# v6_io_23_24_25_26.net
KiCad netlist of a schematic drawn in Altium Designer
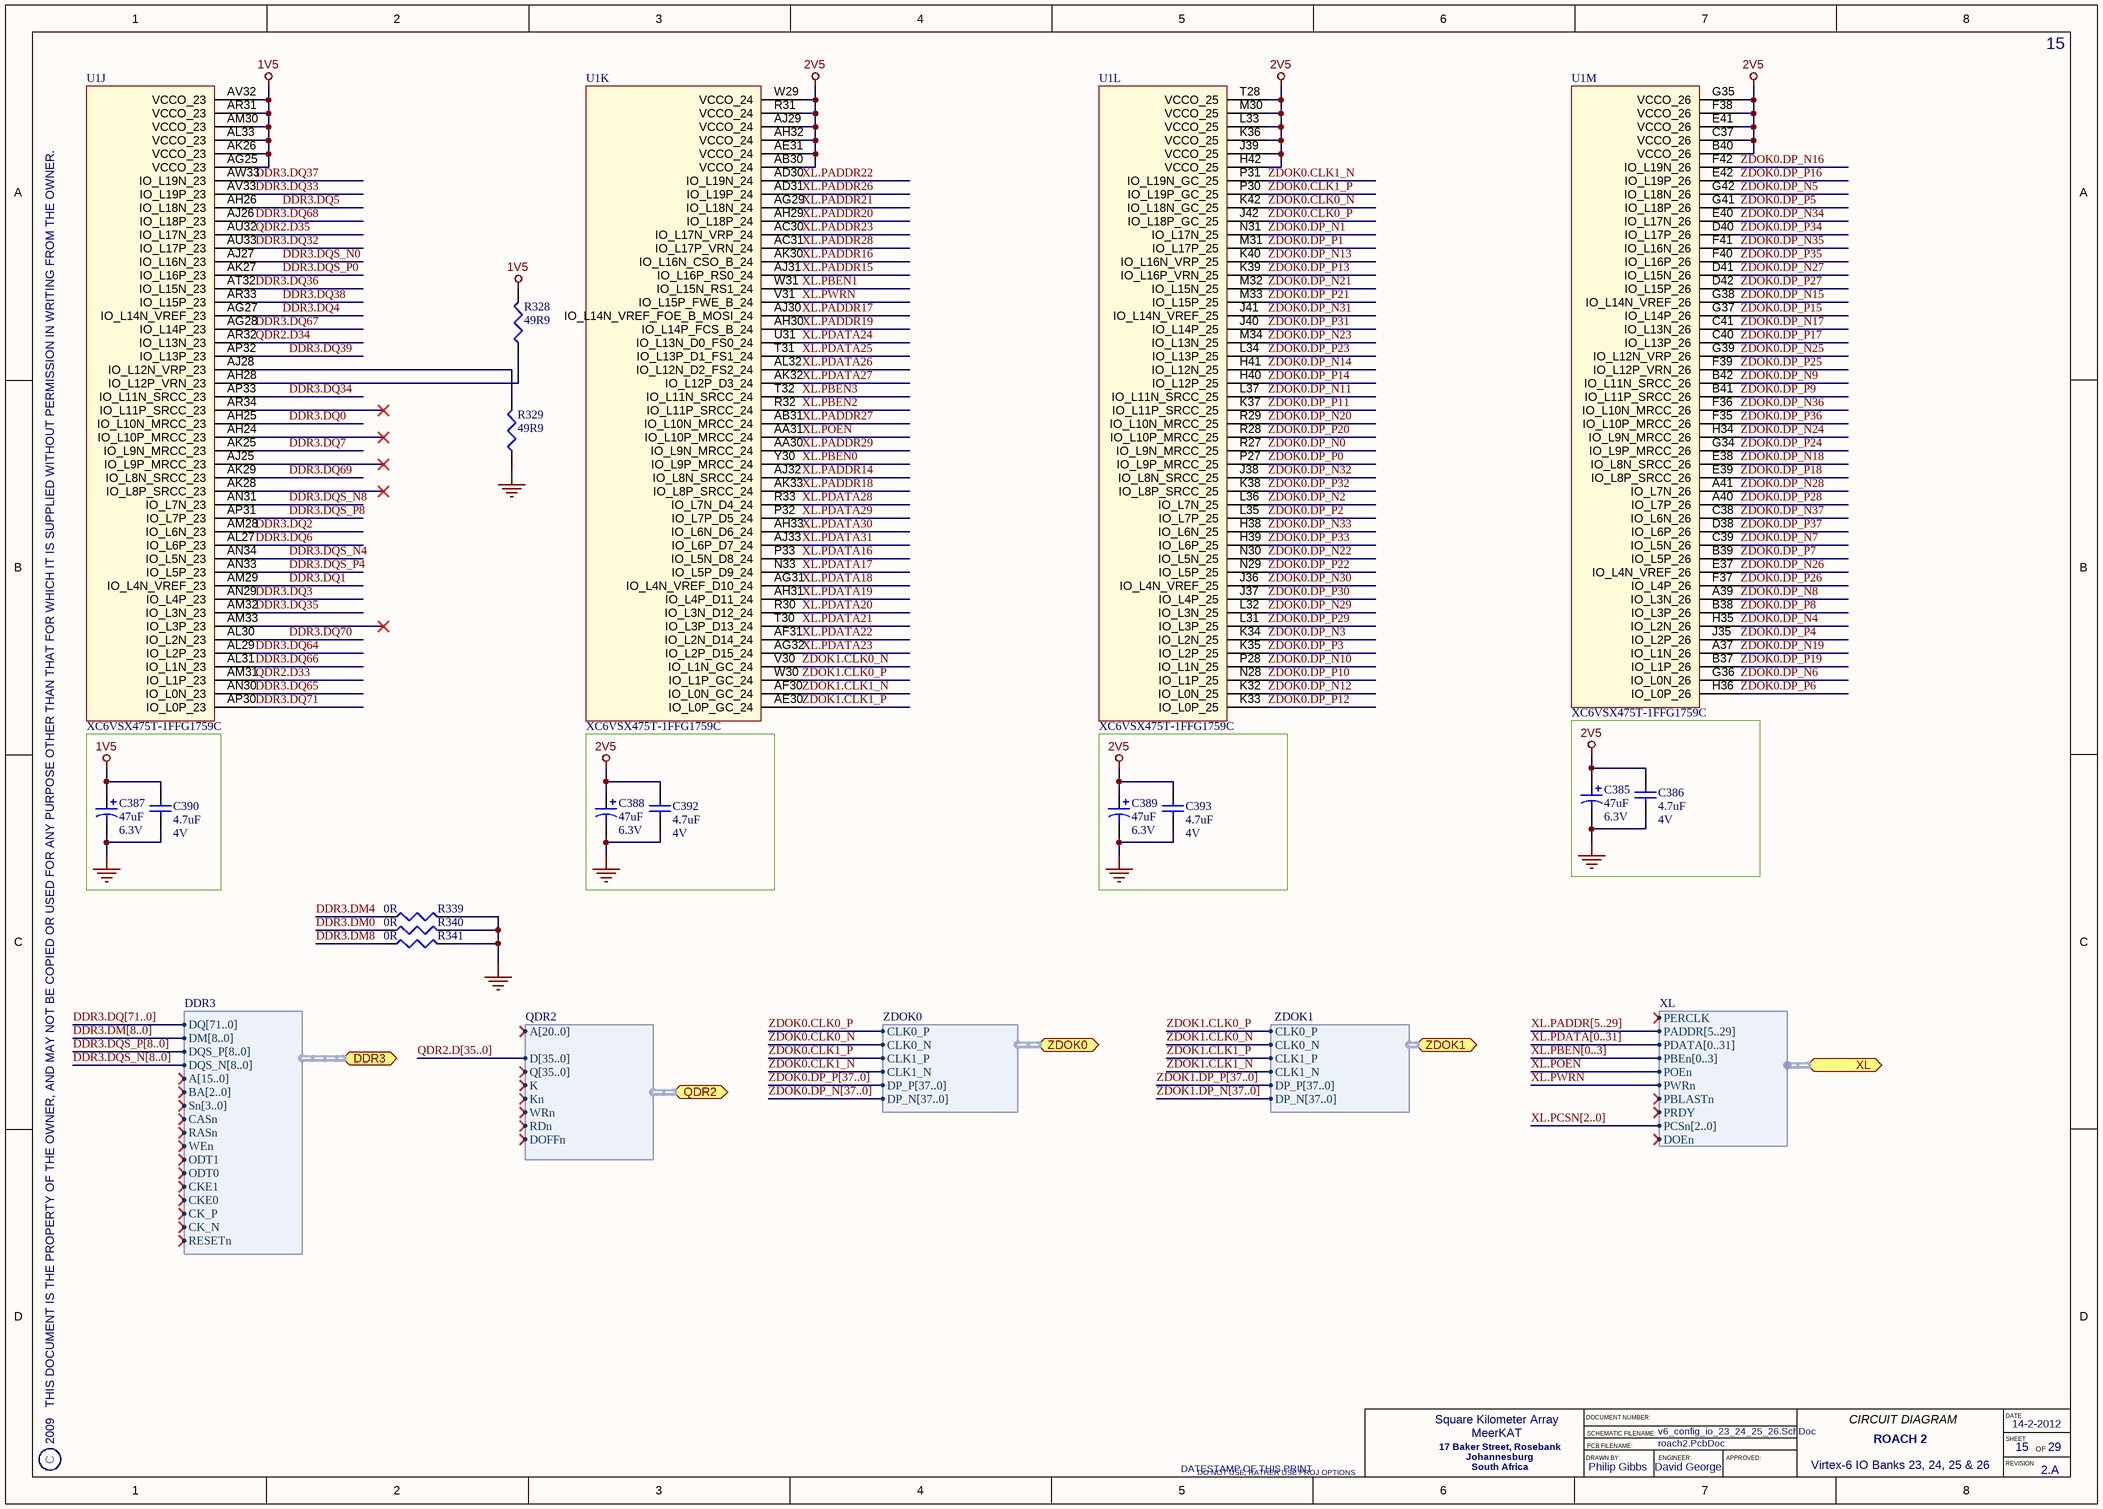
[diagram p0: v6_io_23_24_25_26.SchDoc]

(export (version "E")
  (design (tool "Eeschema 10.0.6"))
  (components
    (comp (ref "C385")
      (value "47uF")
      (footprint "CAPMP3528X120L")
      (description "47uF, Conductive Polymer Chip Capacitor")
      (fields
        (field (name "RATING") "6.3V")
        (field (name "MANUFACTURER") "KEMET")
        (field (name "PARTNUM") "T520T476M006ATE070")
      )
      (libsource (lib "altium_db") (part "CapPol"))
    )
    (comp (ref "C386")
      (value "4.7uF")
      (footprint "CAPC1005X60L")
      (description "4.7uF, Ceramic Capacitor")
      (fields
        (field (name "RATING") "4V")
        (field (name "MANUFACTURER") "MURATA")
        (field (name "PARTNUM") "AMK105BJ475MV-F")
      )
      (libsource (lib "altium_db") (part "CapStd"))
    )
    (comp (ref "C387")
      (value "47uF")
      (footprint "CAPMP3528X120L")
      (description "47uF, Conductive Polymer Chip Capacitor")
      (fields
        (field (name "RATING") "6.3V")
        (field (name "MANUFACTURER") "KEMET")
        (field (name "PARTNUM") "T520T476M006ATE070")
      )
      (libsource (lib "altium_db") (part "CapPol"))
    )
    (comp (ref "C388")
      (value "47uF")
      (footprint "CAPMP3528X120L")
      (description "47uF, Conductive Polymer Chip Capacitor")
      (fields
        (field (name "RATING") "6.3V")
        (field (name "MANUFACTURER") "KEMET")
        (field (name "PARTNUM") "T520T476M006ATE070")
      )
      (libsource (lib "altium_db") (part "CapPol"))
    )
    (comp (ref "C389")
      (value "47uF")
      (footprint "CAPMP3528X120L")
      (description "47uF, Conductive Polymer Chip Capacitor")
      (fields
        (field (name "RATING") "6.3V")
        (field (name "MANUFACTURER") "KEMET")
        (field (name "PARTNUM") "T520T476M006ATE070")
      )
      (libsource (lib "altium_db") (part "CapPol"))
    )
    (comp (ref "C390")
      (value "4.7uF")
      (footprint "CAPC1005X60L")
      (description "4.7uF, Ceramic Capacitor")
      (fields
        (field (name "RATING") "4V")
        (field (name "MANUFACTURER") "MURATA")
        (field (name "PARTNUM") "AMK105BJ475MV-F")
      )
      (libsource (lib "altium_db") (part "CapStd"))
    )
    (comp (ref "C392")
      (value "4.7uF")
      (footprint "CAPC1005X60L")
      (description "4.7uF, Ceramic Capacitor")
      (fields
        (field (name "RATING") "4V")
        (field (name "MANUFACTURER") "MURATA")
        (field (name "PARTNUM") "AMK105BJ475MV-F")
      )
      (libsource (lib "altium_db") (part "CapStd"))
    )
    (comp (ref "C393")
      (value "4.7uF")
      (footprint "CAPC1005X60L")
      (description "4.7uF, Ceramic Capacitor")
      (fields
        (field (name "RATING") "4V")
        (field (name "MANUFACTURER") "MURATA")
        (field (name "PARTNUM") "AMK105BJ475MV-F")
      )
      (libsource (lib "altium_db") (part "CapStd"))
    )
    (comp (ref "R328")
      (value "49R9")
      (footprint "RESC1005X40L")
      (description "49R9, 1.1mm x 0.5mm, Thick Film Resistor")
      (fields (field (name "MANUFACTURER") "ROYALOHM") (field (name "PARTNUM") "0402WGF499JT1E"))
      (libsource (lib "altium_db") (part "ResStd"))
    )
    (comp (ref "R329")
      (value "49R9")
      (footprint "RESC1005X40L")
      (description "49R9, 1.1mm x 0.5mm, Thick Film Resistor")
      (fields (field (name "MANUFACTURER") "ROYALOHM") (field (name "PARTNUM") "0402WGF499JT1E"))
      (libsource (lib "altium_db") (part "ResStd"))
    )
    (comp (ref "R339")
      (value "0R")
      (footprint "RESC1005X40L")
      (description "0R, 1.1mm x 0.5mm, Thick Film Resistor")
      (fields (field (name "MANUFACTURER") "ROYALOHM") (field (name "PARTNUM") "0402WG00000T1E"))
      (libsource (lib "altium_db") (part "ResStd"))
    )
    (comp (ref "R340")
      (value "0R")
      (footprint "RESC1005X40L")
      (description "0R, 1.1mm x 0.5mm, Thick Film Resistor")
      (fields (field (name "MANUFACTURER") "ROYALOHM") (field (name "PARTNUM") "0402WG00000T1E"))
      (libsource (lib "altium_db") (part "ResStd"))
    )
    (comp (ref "R341")
      (value "0R")
      (footprint "RESC1005X40L")
      (description "0R, 1.1mm x 0.5mm, Thick Film Resistor")
      (fields (field (name "MANUFACTURER") "ROYALOHM") (field (name "PARTNUM") "0402WG00000T1E"))
      (libsource (lib "altium_db") (part "ResStd"))
    )
    (comp (ref "U1")
      (value "XC6VSX475T-1FFG1759C")
      (footprint "FFG1759")
      (description "Virtex-6 475SXT 1760-pin FPGA")
      (fields (field (name "MANUFACTURER") "Xilinx"))
      (libsource (lib "altium_db") (part "XC6VSX475T-1FFG1759C"))
    )
  )
  (nets
    (net (code "170") (name "/DDR3.DM0") (class "Default")
      (node (ref "R340") (pin "1") (pinfunction "1_1") (pintype "passive"))
    )
    (net (code "171") (name "/DDR3.DM4") (class "Default")
      (node (ref "R339") (pin "1") (pinfunction "1_1") (pintype "passive"))
    )
    (net (code "172") (name "/DDR3.DM8") (class "Default")
      (node (ref "R341") (pin "1") (pinfunction "1_1") (pintype "passive"))
    )
    (net (code "174") (name "/DDR3.DQ0") (class "Default")
      (node (ref "U1") (pin "AH25") (pinfunction "IO_L10N_MRCC_23_AH25") (pintype "passive"))
    )
    (net (code "175") (name "/DDR3.DQ1") (class "Default")
      (node (ref "U1") (pin "AM29") (pinfunction "IO_L4N_VREF_23_AM29") (pintype "passive"))
    )
    (net (code "176") (name "/DDR3.DQ2") (class "Default")
      (node (ref "U1") (pin "AM28") (pinfunction "IO_L6N_23_AM28") (pintype "passive"))
    )
    (net (code "177") (name "/DDR3.DQ3") (class "Default")
      (node (ref "U1") (pin "AN29") (pinfunction "IO_L4P_23_AN29") (pintype "passive"))
    )
    (net (code "178") (name "/DDR3.DQ4") (class "Default")
      (node (ref "U1") (pin "AG27") (pinfunction "IO_L14N_VREF_23_AG27") (pintype "passive"))
    )
    (net (code "179") (name "/DDR3.DQ5") (class "Default")
      (node (ref "U1") (pin "AH26") (pinfunction "IO_L18N_23_AH26") (pintype "passive"))
    )
    (net (code "180") (name "/DDR3.DQ6") (class "Default")
      (node (ref "U1") (pin "AL27") (pinfunction "IO_L6P_23_AL27") (pintype "passive"))
    )
    (net (code "181") (name "/DDR3.DQ7") (class "Default")
      (node (ref "U1") (pin "AK25") (pinfunction "IO_L9N_MRCC_23_AK25") (pintype "passive"))
    )
    (net (code "182") (name "/DDR3.DQ32") (class "Default")
      (node (ref "U1") (pin "AU33") (pinfunction "IO_L17P_23_AU33") (pintype "passive"))
    )
    (net (code "183") (name "/DDR3.DQ33") (class "Default")
      (node (ref "U1") (pin "AV33") (pinfunction "IO_L19P_23_AV33") (pintype "passive"))
    )
    (net (code "184") (name "/DDR3.DQ34") (class "Default")
      (node (ref "U1") (pin "AP33") (pinfunction "IO_L11N_SRCC_23_AP33") (pintype "passive"))
    )
    (net (code "185") (name "/DDR3.DQ35") (class "Default")
      (node (ref "U1") (pin "AM32") (pinfunction "IO_L3N_23_AM32") (pintype "passive"))
    )
    (net (code "186") (name "/DDR3.DQ36") (class "Default")
      (node (ref "U1") (pin "AT32") (pinfunction "IO_L15N_23_AT32") (pintype "passive"))
    )
    (net (code "187") (name "/DDR3.DQ37") (class "Default")
      (node (ref "U1") (pin "AW33") (pinfunction "IO_L19N_23_AW33") (pintype "passive"))
    )
    (net (code "188") (name "/DDR3.DQ38") (class "Default")
      (node (ref "U1") (pin "AR33") (pinfunction "IO_L15P_23_AR33") (pintype "passive"))
    )
    (net (code "189") (name "/DDR3.DQ39") (class "Default")
      (node (ref "U1") (pin "AP32") (pinfunction "IO_L13P_23_AP32") (pintype "passive"))
    )
    (net (code "190") (name "/DDR3.DQ64") (class "Default")
      (node (ref "U1") (pin "AL29") (pinfunction "IO_L2P_23_AL29") (pintype "passive"))
    )
    (net (code "191") (name "/DDR3.DQ65") (class "Default")
      (node (ref "U1") (pin "AN30") (pinfunction "IO_L0N_23_AN30") (pintype "passive"))
    )
    (net (code "192") (name "/DDR3.DQ66") (class "Default")
      (node (ref "U1") (pin "AL31") (pinfunction "IO_L1N_23_AL31") (pintype "passive"))
    )
    (net (code "193") (name "/DDR3.DQ67") (class "Default")
      (node (ref "U1") (pin "AG28") (pinfunction "IO_L14P_23_AG28") (pintype "passive"))
    )
    (net (code "194") (name "/DDR3.DQ68") (class "Default")
      (node (ref "U1") (pin "AJ26") (pinfunction "IO_L18P_23_AJ26") (pintype "passive"))
    )
    (net (code "195") (name "/DDR3.DQ69") (class "Default")
      (node (ref "U1") (pin "AK29") (pinfunction "IO_L8N_SRCC_23_AK29") (pintype "passive"))
    )
    (net (code "196") (name "/DDR3.DQ70") (class "Default")
      (node (ref "U1") (pin "AL30") (pinfunction "IO_L2N_23_AL30") (pintype "passive"))
    )
    (net (code "197") (name "/DDR3.DQ71") (class "Default")
      (node (ref "U1") (pin "AP30") (pinfunction "IO_L0P_23_AP30") (pintype "passive"))
    )
    (net (code "198") (name "/DDR3.DQS_N0") (class "Default")
      (node (ref "U1") (pin "AJ27") (pinfunction "IO_L16N_23_AJ27") (pintype "passive"))
    )
    (net (code "199") (name "/DDR3.DQS_N4") (class "Default")
      (node (ref "U1") (pin "AN34") (pinfunction "IO_L5N_23_AN34") (pintype "passive"))
    )
    (net (code "200") (name "/DDR3.DQS_N8") (class "Default")
      (node (ref "U1") (pin "AN31") (pinfunction "IO_L7N_23_AN31") (pintype "passive"))
    )
    (net (code "202") (name "/DDR3.DQS_P0") (class "Default")
      (node (ref "U1") (pin "AK27") (pinfunction "IO_L16P_23_AK27") (pintype "passive"))
    )
    (net (code "203") (name "/DDR3.DQS_P4") (class "Default")
      (node (ref "U1") (pin "AN33") (pinfunction "IO_L5P_23_AN33") (pintype "passive"))
    )
    (net (code "204") (name "/DDR3.DQS_P8") (class "Default")
      (node (ref "U1") (pin "AP31") (pinfunction "IO_L7P_23_AP31") (pintype "passive"))
    )
    (net (code "207") (name "/QDR2.D33") (class "Default")
      (node (ref "U1") (pin "AM31") (pinfunction "IO_L1P_23_AM31") (pintype "passive"))
    )
    (net (code "208") (name "/QDR2.D34") (class "Default")
      (node (ref "U1") (pin "AR32") (pinfunction "IO_L13N_23_AR32") (pintype "passive"))
    )
    (net (code "209") (name "/QDR2.D35") (class "Default")
      (node (ref "U1") (pin "AU32") (pinfunction "IO_L17N_23_AU32") (pintype "passive"))
    )
    (net (code "211") (name "/XL.PADDR14") (class "Default")
      (node (ref "U1") (pin "AJ32") (pinfunction "IO_L8N_SRCC_24_AJ32") (pintype "passive"))
    )
    (net (code "212") (name "/XL.PADDR15") (class "Default")
      (node (ref "U1") (pin "AJ31") (pinfunction "IO_L16P_RS0_24_AJ31") (pintype "passive"))
    )
    (net (code "213") (name "/XL.PADDR16") (class "Default")
      (node (ref "U1") (pin "AK30") (pinfunction "IO_L16N_CSO_B_24_AK30") (pintype "passive"))
    )
    (net (code "214") (name "/XL.PADDR17") (class "Default")
      (node (ref "U1") (pin "AJ30") (pinfunction "IO_L14N_VREF_FOE_B_MOSI_24_AJ30") (pintype "passive"))
    )
    (net (code "215") (name "/XL.PADDR18") (class "Default")
      (node (ref "U1") (pin "AK33") (pinfunction "IO_L8P_SRCC_24_AK33") (pintype "passive"))
    )
    (net (code "216") (name "/XL.PADDR19") (class "Default")
      (node (ref "U1") (pin "AH30") (pinfunction "IO_L14P_FCS_B_24_AH30") (pintype "passive"))
    )
    (net (code "217") (name "/XL.PADDR20") (class "Default")
      (node (ref "U1") (pin "AH29") (pinfunction "IO_L18P_24_AH29") (pintype "passive"))
    )
    (net (code "218") (name "/XL.PADDR21") (class "Default")
      (node (ref "U1") (pin "AG29") (pinfunction "IO_L18N_24_AG29") (pintype "passive"))
    )
    (net (code "219") (name "/XL.PADDR22") (class "Default")
      (node (ref "U1") (pin "AD30") (pinfunction "IO_L19N_24_AD30") (pintype "passive"))
    )
    (net (code "220") (name "/XL.PADDR23") (class "Default")
      (node (ref "U1") (pin "AC30") (pinfunction "IO_L17N_VRP_24_AC30") (pintype "passive"))
    )
    (net (code "221") (name "/XL.PADDR26") (class "Default")
      (node (ref "U1") (pin "AD31") (pinfunction "IO_L19P_24_AD31") (pintype "passive"))
    )
    (net (code "222") (name "/XL.PADDR27") (class "Default")
      (node (ref "U1") (pin "AB31") (pinfunction "IO_L10N_MRCC_24_AB31") (pintype "passive"))
    )
    (net (code "223") (name "/XL.PADDR28") (class "Default")
      (node (ref "U1") (pin "AC31") (pinfunction "IO_L17P_VRN_24_AC31") (pintype "passive"))
    )
    (net (code "224") (name "/XL.PADDR29") (class "Default")
      (node (ref "U1") (pin "AA30") (pinfunction "IO_L9N_MRCC_24_AA30") (pintype "passive"))
    )
    (net (code "226") (name "/XL.PBEN0") (class "Default")
      (node (ref "U1") (pin "Y30") (pinfunction "IO_L9P_MRCC_24_Y30") (pintype "passive"))
    )
    (net (code "227") (name "/XL.PBEN1") (class "Default")
      (node (ref "U1") (pin "W31") (pinfunction "IO_L15N_RS1_24_W31") (pintype "passive"))
    )
    (net (code "228") (name "/XL.PBEN2") (class "Default")
      (node (ref "U1") (pin "R32") (pinfunction "IO_L11P_SRCC_24_R32") (pintype "passive"))
    )
    (net (code "229") (name "/XL.PBEN3") (class "Default")
      (node (ref "U1") (pin "T32") (pinfunction "IO_L11N_SRCC_24_T32") (pintype "passive"))
    )
    (net (code "231") (name "/XL.PDATA16") (class "Default")
      (node (ref "U1") (pin "P33") (pinfunction "IO_L5N_D8_24_P33") (pintype "passive"))
    )
    (net (code "232") (name "/XL.PDATA17") (class "Default")
      (node (ref "U1") (pin "N33") (pinfunction "IO_L5P_D9_24_N33") (pintype "passive"))
    )
    (net (code "233") (name "/XL.PDATA18") (class "Default")
      (node (ref "U1") (pin "AG31") (pinfunction "IO_L4N_VREF_D10_24_AG31") (pintype "passive"))
    )
    (net (code "234") (name "/XL.PDATA19") (class "Default")
      (node (ref "U1") (pin "AH31") (pinfunction "IO_L4P_D11_24_AH31") (pintype "passive"))
    )
    (net (code "235") (name "/XL.PDATA20") (class "Default")
      (node (ref "U1") (pin "R30") (pinfunction "IO_L3N_D12_24_R30") (pintype "passive"))
    )
    (net (code "236") (name "/XL.PDATA21") (class "Default")
      (node (ref "U1") (pin "T30") (pinfunction "IO_L3P_D13_24_T30") (pintype "passive"))
    )
    (net (code "237") (name "/XL.PDATA22") (class "Default")
      (node (ref "U1") (pin "AF31") (pinfunction "IO_L2N_D14_24_AF31") (pintype "passive"))
    )
    (net (code "238") (name "/XL.PDATA23") (class "Default")
      (node (ref "U1") (pin "AG32") (pinfunction "IO_L2P_D15_24_AG32") (pintype "passive"))
    )
    (net (code "239") (name "/XL.PDATA24") (class "Default")
      (node (ref "U1") (pin "U31") (pinfunction "IO_L13N_D0_FS0_24_U31") (pintype "passive"))
    )
    (net (code "240") (name "/XL.PDATA25") (class "Default")
      (node (ref "U1") (pin "T31") (pinfunction "IO_L13P_D1_FS1_24_T31") (pintype "passive"))
    )
    (net (code "241") (name "/XL.PDATA26") (class "Default")
      (node (ref "U1") (pin "AL32") (pinfunction "IO_L12N_D2_FS2_24_AL32") (pintype "passive"))
    )
    (net (code "242") (name "/XL.PDATA27") (class "Default")
      (node (ref "U1") (pin "AK32") (pinfunction "IO_L12P_D3_24_AK32") (pintype "passive"))
    )
    (net (code "243") (name "/XL.PDATA28") (class "Default")
      (node (ref "U1") (pin "R33") (pinfunction "IO_L7N_D4_24_R33") (pintype "passive"))
    )
    (net (code "244") (name "/XL.PDATA29") (class "Default")
      (node (ref "U1") (pin "P32") (pinfunction "IO_L7P_D5_24_P32") (pintype "passive"))
    )
    (net (code "245") (name "/XL.PDATA30") (class "Default")
      (node (ref "U1") (pin "AH33") (pinfunction "IO_L6N_D6_24_AH33") (pintype "passive"))
    )
    (net (code "246") (name "/XL.PDATA31") (class "Default")
      (node (ref "U1") (pin "AJ33") (pinfunction "IO_L6P_D7_24_AJ33") (pintype "passive"))
    )
    (net (code "248") (name "/XL.POEN") (class "Default")
      (node (ref "U1") (pin "AA31") (pinfunction "IO_L10P_MRCC_24_AA31") (pintype "passive"))
    )
    (net (code "249") (name "/XL.PWRN") (class "Default")
      (node (ref "U1") (pin "V31") (pinfunction "IO_L15P_FWE_B_24_V31") (pintype "passive"))
    )
    (net (code "251") (name "/ZDOK0.CLK0_N") (class "Default")
      (node (ref "U1") (pin "K42") (pinfunction "IO_L18N_GC_25_K42") (pintype "passive"))
    )
    (net (code "252") (name "/ZDOK0.CLK0_P") (class "Default")
      (node (ref "U1") (pin "J42") (pinfunction "IO_L18P_GC_25_J42") (pintype "passive"))
    )
    (net (code "253") (name "/ZDOK0.CLK1_N") (class "Default")
      (node (ref "U1") (pin "P31") (pinfunction "IO_L19N_GC_25_P31") (pintype "passive"))
    )
    (net (code "254") (name "/ZDOK0.CLK1_P") (class "Default")
      (node (ref "U1") (pin "P30") (pinfunction "IO_L19P_GC_25_P30") (pintype "passive"))
    )
    (net (code "255") (name "/ZDOK0.DP_N0") (class "Default")
      (node (ref "U1") (pin "R27") (pinfunction "IO_L9N_MRCC_25_R27") (pintype "passive"))
    )
    (net (code "256") (name "/ZDOK0.DP_N1") (class "Default")
      (node (ref "U1") (pin "N31") (pinfunction "IO_L17N_25_N31") (pintype "passive"))
    )
    (net (code "257") (name "/ZDOK0.DP_N2") (class "Default")
      (node (ref "U1") (pin "L36") (pinfunction "IO_L7N_25_L36") (pintype "passive"))
    )
    (net (code "258") (name "/ZDOK0.DP_N3") (class "Default")
      (node (ref "U1") (pin "K34") (pinfunction "IO_L2N_25_K34") (pintype "passive"))
    )
    (net (code "259") (name "/ZDOK0.DP_N4") (class "Default")
      (node (ref "U1") (pin "H35") (pinfunction "IO_L2N_26_H35") (pintype "passive"))
    )
    (net (code "260") (name "/ZDOK0.DP_N5") (class "Default")
      (node (ref "U1") (pin "G42") (pinfunction "IO_L18N_26_G42") (pintype "passive"))
    )
    (net (code "261") (name "/ZDOK0.DP_N6") (class "Default")
      (node (ref "U1") (pin "G36") (pinfunction "IO_L0N_26_G36") (pintype "passive"))
    )
    (net (code "262") (name "/ZDOK0.DP_N7") (class "Default")
      (node (ref "U1") (pin "C39") (pinfunction "IO_L5N_26_C39") (pintype "passive"))
    )
    (net (code "263") (name "/ZDOK0.DP_N8") (class "Default")
      (node (ref "U1") (pin "A39") (pinfunction "IO_L3N_26_A39") (pintype "passive"))
    )
    (net (code "264") (name "/ZDOK0.DP_N9") (class "Default")
      (node (ref "U1") (pin "B42") (pinfunction "IO_L11N_SRCC_26_B42") (pintype "passive"))
    )
    (net (code "265") (name "/ZDOK0.DP_N10") (class "Default")
      (node (ref "U1") (pin "P28") (pinfunction "IO_L1N_25_P28") (pintype "passive"))
    )
    (net (code "266") (name "/ZDOK0.DP_N11") (class "Default")
      (node (ref "U1") (pin "L37") (pinfunction "IO_L11N_SRCC_25_L37") (pintype "passive"))
    )
    (net (code "267") (name "/ZDOK0.DP_N12") (class "Default")
      (node (ref "U1") (pin "K32") (pinfunction "IO_L0N_25_K32") (pintype "passive"))
    )
    (net (code "268") (name "/ZDOK0.DP_N13") (class "Default")
      (node (ref "U1") (pin "K40") (pinfunction "IO_L16N_VRP_25_K40") (pintype "passive"))
    )
    (net (code "269") (name "/ZDOK0.DP_N14") (class "Default")
      (node (ref "U1") (pin "H41") (pinfunction "IO_L12N_25_H41") (pintype "passive"))
    )
    (net (code "270") (name "/ZDOK0.DP_N15") (class "Default")
      (node (ref "U1") (pin "G38") (pinfunction "IO_L14N_VREF_26_G38") (pintype "passive"))
    )
    (net (code "271") (name "/ZDOK0.DP_N16") (class "Default")
      (node (ref "U1") (pin "F42") (pinfunction "IO_L19N_26_F42") (pintype "passive"))
    )
    (net (code "272") (name "/ZDOK0.DP_N17") (class "Default")
      (node (ref "U1") (pin "C41") (pinfunction "IO_L13N_26_C41") (pintype "passive"))
    )
    (net (code "273") (name "/ZDOK0.DP_N18") (class "Default")
      (node (ref "U1") (pin "E38") (pinfunction "IO_L8N_SRCC_26_E38") (pintype "passive"))
    )
    (net (code "274") (name "/ZDOK0.DP_N19") (class "Default")
      (node (ref "U1") (pin "A37") (pinfunction "IO_L1N_26_A37") (pintype "passive"))
    )
    (net (code "275") (name "/ZDOK0.DP_N20") (class "Default")
      (node (ref "U1") (pin "R29") (pinfunction "IO_L10N_MRCC_25_R29") (pintype "passive"))
    )
    (net (code "276") (name "/ZDOK0.DP_N21") (class "Default")
      (node (ref "U1") (pin "M32") (pinfunction "IO_L15N_25_M32") (pintype "passive"))
    )
    (net (code "277") (name "/ZDOK0.DP_N22") (class "Default")
      (node (ref "U1") (pin "N30") (pinfunction "IO_L5N_25_N30") (pintype "passive"))
    )
    (net (code "278") (name "/ZDOK0.DP_N23") (class "Default")
      (node (ref "U1") (pin "M34") (pinfunction "IO_L13N_25_M34") (pintype "passive"))
    )
    (net (code "279") (name "/ZDOK0.DP_N24") (class "Default")
      (node (ref "U1") (pin "H34") (pinfunction "IO_L9N_MRCC_26_H34") (pintype "passive"))
    )
    (net (code "280") (name "/ZDOK0.DP_N25") (class "Default")
      (node (ref "U1") (pin "G39") (pinfunction "IO_L12N_VRP_26_G39") (pintype "passive"))
    )
    (net (code "281") (name "/ZDOK0.DP_N26") (class "Default")
      (node (ref "U1") (pin "E37") (pinfunction "IO_L4N_VREF_26_E37") (pintype "passive"))
    )
    (net (code "282") (name "/ZDOK0.DP_N27") (class "Default")
      (node (ref "U1") (pin "D41") (pinfunction "IO_L15N_26_D41") (pintype "passive"))
    )
    (net (code "283") (name "/ZDOK0.DP_N28") (class "Default")
      (node (ref "U1") (pin "A41") (pinfunction "IO_L7N_26_A41") (pintype "passive"))
    )
    (net (code "284") (name "/ZDOK0.DP_N29") (class "Default")
      (node (ref "U1") (pin "L32") (pinfunction "IO_L3N_25_L32") (pintype "passive"))
    )
    (net (code "285") (name "/ZDOK0.DP_N30") (class "Default")
      (node (ref "U1") (pin "J36") (pinfunction "IO_L4N_VREF_25_J36") (pintype "passive"))
    )
    (net (code "286") (name "/ZDOK0.DP_N31") (class "Default")
      (node (ref "U1") (pin "J41") (pinfunction "IO_L14N_VREF_25_J41") (pintype "passive"))
    )
    (net (code "287") (name "/ZDOK0.DP_N32") (class "Default")
      (node (ref "U1") (pin "J38") (pinfunction "IO_L8N_SRCC_25_J38") (pintype "passive"))
    )
    (net (code "288") (name "/ZDOK0.DP_N33") (class "Default")
      (node (ref "U1") (pin "H38") (pinfunction "IO_L6N_25_H38") (pintype "passive"))
    )
    (net (code "289") (name "/ZDOK0.DP_N34") (class "Default")
      (node (ref "U1") (pin "E40") (pinfunction "IO_L17N_26_E40") (pintype "passive"))
    )
    (net (code "290") (name "/ZDOK0.DP_N35") (class "Default")
      (node (ref "U1") (pin "F41") (pinfunction "IO_L16N_26_F41") (pintype "passive"))
    )
    (net (code "291") (name "/ZDOK0.DP_N36") (class "Default")
      (node (ref "U1") (pin "F36") (pinfunction "IO_L10N_MRCC_26_F36") (pintype "passive"))
    )
    (net (code "292") (name "/ZDOK0.DP_N37") (class "Default")
      (node (ref "U1") (pin "C38") (pinfunction "IO_L6N_26_C38") (pintype "passive"))
    )
    (net (code "294") (name "/ZDOK0.DP_P0") (class "Default")
      (node (ref "U1") (pin "P27") (pinfunction "IO_L9P_MRCC_25_P27") (pintype "passive"))
    )
    (net (code "295") (name "/ZDOK0.DP_P1") (class "Default")
      (node (ref "U1") (pin "M31") (pinfunction "IO_L17P_25_M31") (pintype "passive"))
    )
    (net (code "296") (name "/ZDOK0.DP_P2") (class "Default")
      (node (ref "U1") (pin "L35") (pinfunction "IO_L7P_25_L35") (pintype "passive"))
    )
    (net (code "297") (name "/ZDOK0.DP_P3") (class "Default")
      (node (ref "U1") (pin "K35") (pinfunction "IO_L2P_25_K35") (pintype "passive"))
    )
    (net (code "298") (name "/ZDOK0.DP_P4") (class "Default")
      (node (ref "U1") (pin "J35") (pinfunction "IO_L2P_26_J35") (pintype "passive"))
    )
    (net (code "299") (name "/ZDOK0.DP_P5") (class "Default")
      (node (ref "U1") (pin "G41") (pinfunction "IO_L18P_26_G41") (pintype "passive"))
    )
    (net (code "300") (name "/ZDOK0.DP_P6") (class "Default")
      (node (ref "U1") (pin "H36") (pinfunction "IO_L0P_26_H36") (pintype "passive"))
    )
    (net (code "301") (name "/ZDOK0.DP_P7") (class "Default")
      (node (ref "U1") (pin "B39") (pinfunction "IO_L5P_26_B39") (pintype "passive"))
    )
    (net (code "302") (name "/ZDOK0.DP_P8") (class "Default")
      (node (ref "U1") (pin "B38") (pinfunction "IO_L3P_26_B38") (pintype "passive"))
    )
    (net (code "303") (name "/ZDOK0.DP_P9") (class "Default")
      (node (ref "U1") (pin "B41") (pinfunction "IO_L11P_SRCC_26_B41") (pintype "passive"))
    )
    (net (code "304") (name "/ZDOK0.DP_P10") (class "Default")
      (node (ref "U1") (pin "N28") (pinfunction "IO_L1P_25_N28") (pintype "passive"))
    )
    (net (code "305") (name "/ZDOK0.DP_P11") (class "Default")
      (node (ref "U1") (pin "K37") (pinfunction "IO_L11P_SRCC_25_K37") (pintype "passive"))
    )
    (net (code "306") (name "/ZDOK0.DP_P12") (class "Default")
      (node (ref "U1") (pin "K33") (pinfunction "IO_L0P_25_K33") (pintype "passive"))
    )
    (net (code "307") (name "/ZDOK0.DP_P13") (class "Default")
      (node (ref "U1") (pin "K39") (pinfunction "IO_L16P_VRN_25_K39") (pintype "passive"))
    )
    (net (code "308") (name "/ZDOK0.DP_P14") (class "Default")
      (node (ref "U1") (pin "H40") (pinfunction "IO_L12P_25_H40") (pintype "passive"))
    )
    (net (code "309") (name "/ZDOK0.DP_P15") (class "Default")
      (node (ref "U1") (pin "G37") (pinfunction "IO_L14P_26_G37") (pintype "passive"))
    )
    (net (code "310") (name "/ZDOK0.DP_P16") (class "Default")
      (node (ref "U1") (pin "E42") (pinfunction "IO_L19P_26_E42") (pintype "passive"))
    )
    (net (code "311") (name "/ZDOK0.DP_P17") (class "Default")
      (node (ref "U1") (pin "C40") (pinfunction "IO_L13P_26_C40") (pintype "passive"))
    )
    (net (code "312") (name "/ZDOK0.DP_P18") (class "Default")
      (node (ref "U1") (pin "E39") (pinfunction "IO_L8P_SRCC_26_E39") (pintype "passive"))
    )
    (net (code "313") (name "/ZDOK0.DP_P19") (class "Default")
      (node (ref "U1") (pin "B37") (pinfunction "IO_L1P_26_B37") (pintype "passive"))
    )
    (net (code "314") (name "/ZDOK0.DP_P20") (class "Default")
      (node (ref "U1") (pin "R28") (pinfunction "IO_L10P_MRCC_25_R28") (pintype "passive"))
    )
    (net (code "315") (name "/ZDOK0.DP_P21") (class "Default")
      (node (ref "U1") (pin "M33") (pinfunction "IO_L15P_25_M33") (pintype "passive"))
    )
    (net (code "316") (name "/ZDOK0.DP_P22") (class "Default")
      (node (ref "U1") (pin "N29") (pinfunction "IO_L5P_25_N29") (pintype "passive"))
    )
    (net (code "317") (name "/ZDOK0.DP_P23") (class "Default")
      (node (ref "U1") (pin "L34") (pinfunction "IO_L13P_25_L34") (pintype "passive"))
    )
    (net (code "318") (name "/ZDOK0.DP_P24") (class "Default")
      (node (ref "U1") (pin "G34") (pinfunction "IO_L9P_MRCC_26_G34") (pintype "passive"))
    )
    (net (code "319") (name "/ZDOK0.DP_P25") (class "Default")
      (node (ref "U1") (pin "F39") (pinfunction "IO_L12P_VRN_26_F39") (pintype "passive"))
    )
    (net (code "320") (name "/ZDOK0.DP_P26") (class "Default")
      (node (ref "U1") (pin "F37") (pinfunction "IO_L4P_26_F37") (pintype "passive"))
    )
    (net (code "321") (name "/ZDOK0.DP_P27") (class "Default")
      (node (ref "U1") (pin "D42") (pinfunction "IO_L15P_26_D42") (pintype "passive"))
    )
    (net (code "322") (name "/ZDOK0.DP_P28") (class "Default")
      (node (ref "U1") (pin "A40") (pinfunction "IO_L7P_26_A40") (pintype "passive"))
    )
    (net (code "323") (name "/ZDOK0.DP_P29") (class "Default")
      (node (ref "U1") (pin "L31") (pinfunction "IO_L3P_25_L31") (pintype "passive"))
    )
    (net (code "324") (name "/ZDOK0.DP_P30") (class "Default")
      (node (ref "U1") (pin "J37") (pinfunction "IO_L4P_25_J37") (pintype "passive"))
    )
    (net (code "325") (name "/ZDOK0.DP_P31") (class "Default")
      (node (ref "U1") (pin "J40") (pinfunction "IO_L14P_25_J40") (pintype "passive"))
    )
    (net (code "326") (name "/ZDOK0.DP_P32") (class "Default")
      (node (ref "U1") (pin "K38") (pinfunction "IO_L8P_SRCC_25_K38") (pintype "passive"))
    )
    (net (code "327") (name "/ZDOK0.DP_P33") (class "Default")
      (node (ref "U1") (pin "H39") (pinfunction "IO_L6P_25_H39") (pintype "passive"))
    )
    (net (code "328") (name "/ZDOK0.DP_P34") (class "Default")
      (node (ref "U1") (pin "D40") (pinfunction "IO_L17P_26_D40") (pintype "passive"))
    )
    (net (code "329") (name "/ZDOK0.DP_P35") (class "Default")
      (node (ref "U1") (pin "F40") (pinfunction "IO_L16P_26_F40") (pintype "passive"))
    )
    (net (code "330") (name "/ZDOK0.DP_P36") (class "Default")
      (node (ref "U1") (pin "F35") (pinfunction "IO_L10P_MRCC_26_F35") (pintype "passive"))
    )
    (net (code "331") (name "/ZDOK0.DP_P37") (class "Default")
      (node (ref "U1") (pin "D38") (pinfunction "IO_L6P_26_D38") (pintype "passive"))
    )
    (net (code "333") (name "/ZDOK1.CLK0_N") (class "Default")
      (node (ref "U1") (pin "V30") (pinfunction "IO_L1N_GC_24_V30") (pintype "passive"))
    )
    (net (code "334") (name "/ZDOK1.CLK0_P") (class "Default")
      (node (ref "U1") (pin "W30") (pinfunction "IO_L1P_GC_24_W30") (pintype "passive"))
    )
    (net (code "335") (name "/ZDOK1.CLK1_N") (class "Default")
      (node (ref "U1") (pin "AF30") (pinfunction "IO_L0N_GC_24_AF30") (pintype "passive"))
    )
    (net (code "336") (name "/ZDOK1.CLK1_P") (class "Default")
      (node (ref "U1") (pin "AE30") (pinfunction "IO_L0P_GC_24_AE30") (pintype "passive"))
    )
    (net (code "343") (name "1V5") (class "Default")
      (node (ref "C387") (pin "1") (pinfunction "1_1") (pintype "passive"))
      (node (ref "C390") (pin "2") (pinfunction "2_2") (pintype "passive"))
      (node (ref "R328") (pin "2") (pinfunction "2_2") (pintype "passive"))
      (node (ref "U1") (pin "AG25") (pinfunction "VCCO_23_AG25") (pintype "passive"))
      (node (ref "U1") (pin "AK26") (pinfunction "VCCO_23_AK26") (pintype "passive"))
      (node (ref "U1") (pin "AL33") (pinfunction "VCCO_23_AL33") (pintype "passive"))
      (node (ref "U1") (pin "AM30") (pinfunction "VCCO_23_AM30") (pintype "passive"))
      (node (ref "U1") (pin "AR31") (pinfunction "VCCO_23_AR31") (pintype "passive"))
      (node (ref "U1") (pin "AV32") (pinfunction "VCCO_23_AV32") (pintype "passive"))
    )
    (net (code "344") (name "2V5") (class "Default")
      (node (ref "C385") (pin "1") (pinfunction "1_1") (pintype "passive"))
      (node (ref "C386") (pin "2") (pinfunction "2_2") (pintype "passive"))
      (node (ref "C388") (pin "1") (pinfunction "1_1") (pintype "passive"))
      (node (ref "C389") (pin "1") (pinfunction "1_1") (pintype "passive"))
      (node (ref "C392") (pin "2") (pinfunction "2_2") (pintype "passive"))
      (node (ref "C393") (pin "2") (pinfunction "2_2") (pintype "passive"))
      (node (ref "U1") (pin "AB30") (pinfunction "VCCO_24_AB30") (pintype "passive"))
      (node (ref "U1") (pin "AE31") (pinfunction "VCCO_24_AE31") (pintype "passive"))
      (node (ref "U1") (pin "AH32") (pinfunction "VCCO_24_AH32") (pintype "passive"))
      (node (ref "U1") (pin "AJ29") (pinfunction "VCCO_24_AJ29") (pintype "passive"))
      (node (ref "U1") (pin "B40") (pinfunction "VCCO_26_B40") (pintype "passive"))
      (node (ref "U1") (pin "C37") (pinfunction "VCCO_26_C37") (pintype "passive"))
      (node (ref "U1") (pin "E41") (pinfunction "VCCO_26_E41") (pintype "passive"))
      (node (ref "U1") (pin "F38") (pinfunction "VCCO_26_F38") (pintype "passive"))
      (node (ref "U1") (pin "G35") (pinfunction "VCCO_26_G35") (pintype "passive"))
      (node (ref "U1") (pin "H42") (pinfunction "VCCO_25_H42") (pintype "passive"))
      (node (ref "U1") (pin "J39") (pinfunction "VCCO_25_J39") (pintype "passive"))
      (node (ref "U1") (pin "K36") (pinfunction "VCCO_25_K36") (pintype "passive"))
      (node (ref "U1") (pin "L33") (pinfunction "VCCO_25_L33") (pintype "passive"))
      (node (ref "U1") (pin "M30") (pinfunction "VCCO_25_M30") (pintype "passive"))
      (node (ref "U1") (pin "R31") (pinfunction "VCCO_24_R31") (pintype "passive"))
      (node (ref "U1") (pin "T28") (pinfunction "VCCO_25_T28") (pintype "passive"))
      (node (ref "U1") (pin "W29") (pinfunction "VCCO_24_W29") (pintype "passive"))
    )
    (net (code "345") (name "GND") (class "Default")
      (node (ref "C385") (pin "2") (pinfunction "2_2") (pintype "passive"))
      (node (ref "C386") (pin "1") (pinfunction "1_1") (pintype "passive"))
      (node (ref "C387") (pin "2") (pinfunction "2_2") (pintype "passive"))
      (node (ref "C388") (pin "2") (pinfunction "2_2") (pintype "passive"))
      (node (ref "C389") (pin "2") (pinfunction "2_2") (pintype "passive"))
      (node (ref "C390") (pin "1") (pinfunction "1_1") (pintype "passive"))
      (node (ref "C392") (pin "1") (pinfunction "1_1") (pintype "passive"))
      (node (ref "C393") (pin "1") (pinfunction "1_1") (pintype "passive"))
      (node (ref "R329") (pin "1") (pinfunction "1_1") (pintype "passive"))
      (node (ref "R339") (pin "2") (pinfunction "2_2") (pintype "passive"))
      (node (ref "R340") (pin "2") (pinfunction "2_2") (pintype "passive"))
      (node (ref "R341") (pin "2") (pinfunction "2_2") (pintype "passive"))
    )
    (net (code "346") (name "Net-(U1J-IO_L12N_VRP_23)") (class "Default")
      (node (ref "R329") (pin "2") (pinfunction "2_2") (pintype "passive"))
      (node (ref "U1") (pin "AJ28") (pinfunction "IO_L12N_VRP_23_AJ28") (pintype "passive"))
    )
    (net (code "347") (name "Net-(U1J-IO_L12P_VRN_23)") (class "Default")
      (node (ref "R328") (pin "1") (pinfunction "1_1") (pintype "passive"))
      (node (ref "U1") (pin "AH28") (pinfunction "IO_L12P_VRN_23_AH28") (pintype "passive"))
    )
    (net (code "348") (name "unconnected-(U1J-IO_L3P_23-PadAM33)") (class "Default")
      (node (ref "U1") (pin "AM33") (pinfunction "IO_L3P_23_AM33") (pintype "passive+no_connect"))
    )
    (net (code "349") (name "unconnected-(U1J-IO_L8P_SRCC_23-PadAK28)") (class "Default")
      (node (ref "U1") (pin "AK28") (pinfunction "IO_L8P_SRCC_23_AK28") (pintype "passive+no_connect"))
    )
    (net (code "350") (name "unconnected-(U1J-IO_L9P_MRCC_23-PadAJ25)") (class "Default")
      (node (ref "U1") (pin "AJ25") (pinfunction "IO_L9P_MRCC_23_AJ25") (pintype "passive+no_connect"))
    )
    (net (code "351") (name "unconnected-(U1J-IO_L10P_MRCC_23-PadAH24)") (class "Default")
      (node (ref "U1") (pin "AH24") (pinfunction "IO_L10P_MRCC_23_AH24") (pintype "passive+no_connect"))
    )
    (net (code "352") (name "unconnected-(U1J-IO_L11P_SRCC_23-PadAR34)") (class "Default")
      (node (ref "U1") (pin "AR34") (pinfunction "IO_L11P_SRCC_23_AR34") (pintype "passive+no_connect"))
    )
  )
)
